# Magnetometer.net
KiCad netlist of a schematic drawn in Altium Designer
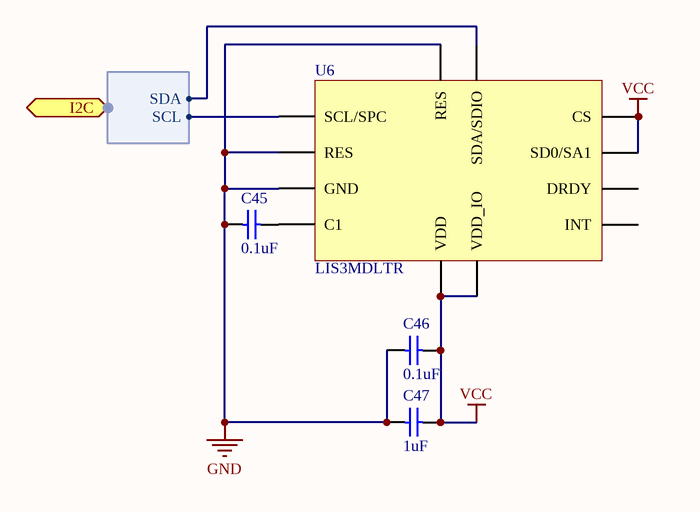
[diagram p0: Magnetometer.SchDoc]

(export (version "E")
  (design (tool "Eeschema 10.0.6"))
  (components
    (comp (ref "C45")
      (value "0.1uF")
      (footprint "C0402[1005X55]")
      (description "0.1uF 6.3V 10% 0402 (1005 Metric)")
      (fields (field (name "PARTNUMBER") "GRM155R70J104KA01D") (field (name "MANUFACTURER") "Murata"))
      (libsource (lib "Capacitors") (part "CAP_0.1uF_6.3V_0402_10%"))
    )
    (comp (ref "C46")
      (value "0.1uF")
      (footprint "C0402[1005X55]")
      (description "0.1uF 6.3V 10% 0402 (1005 Metric)")
      (fields (field (name "PARTNUMBER") "GRM155R70J104KA01D") (field (name "MANUFACTURER") "Murata"))
      (libsource (lib "Capacitors") (part "CAP_0.1uF_6.3V_0402_10%"))
    )
    (comp (ref "C47")
      (value "1uF")
      (footprint "C0402[1005X55]")
      (description "1uF 6.3V 10% 0402 (1005 Metric)")
      (fields (field (name "PARTNUMBER") "GRM155R70J105KA12D") (field (name "MANUFACTURER") "Murata"))
      (libsource (lib "Capacitors") (part "CAP_1uF_6.3V_0402_10%"))
    )
    (comp (ref "U6")
      (value "LIS3MDLTR")
      (footprint "LGA-12 (2x2MM)")
      (description "Board Mount Hall Effect / Magnetic Sensors Ultra Lo-Pwr Hi Perf 3-Axis 1.9-3.6V")
      (fields (field (name "MANUFACTURER") "STMicroelectronics"))
      (libsource (lib "ICs") (part "LIS3MDLTR"))
    )
  )
  (nets
    (net (code "2") (name "/SCL") (class "Default")
      (node (ref "U6") (pin "1") (pinfunction "SCL/SPC_1") (pintype "passive"))
    )
    (net (code "3") (name "/SDA") (class "Default")
      (node (ref "U6") (pin "11") (pinfunction "SDA/SDIO_11") (pintype "passive"))
    )
    (net (code "5") (name "GND") (class "Default")
      (node (ref "C45") (pin "1") (pinfunction "1_1") (pintype "passive"))
      (node (ref "C46") (pin "1") (pinfunction "1_1") (pintype "passive"))
      (node (ref "C47") (pin "1") (pinfunction "1_1") (pintype "passive"))
      (node (ref "U6") (pin "12") (pinfunction "RES_12") (pintype "passive"))
      (node (ref "U6") (pin "2") (pinfunction "RES_2") (pintype "passive"))
      (node (ref "U6") (pin "3") (pinfunction "GND_3") (pintype "passive"))
    )
    (net (code "6") (name "Net-(U6-C1)") (class "Default")
      (node (ref "C45") (pin "2") (pinfunction "2_2") (pintype "passive"))
      (node (ref "U6") (pin "4") (pinfunction "C1_4") (pintype "passive"))
    )
    (net (code "7") (name "VCC") (class "Default")
      (node (ref "C46") (pin "2") (pinfunction "2_2") (pintype "passive"))
      (node (ref "C47") (pin "2") (pinfunction "2_2") (pintype "passive"))
      (node (ref "U6") (pin "10") (pinfunction "CS_10") (pintype "passive"))
      (node (ref "U6") (pin "5") (pinfunction "VDD_5") (pintype "passive"))
      (node (ref "U6") (pin "6") (pinfunction "VDD_IO_6") (pintype "passive"))
      (node (ref "U6") (pin "9") (pinfunction "SD0/SA1_9") (pintype "passive"))
    )
    (net (code "8") (name "unconnected-(U6-DRDY-Pad8)") (class "Default")
      (node (ref "U6") (pin "8") (pinfunction "DRDY_8") (pintype "passive"))
    )
    (net (code "9") (name "unconnected-(U6-INT-Pad7)") (class "Default")
      (node (ref "U6") (pin "7") (pinfunction "INT_7") (pintype "passive"))
    )
  )
)
